# mast_panel_board.net
KiCad netlist of a schematic drawn in EAGLE
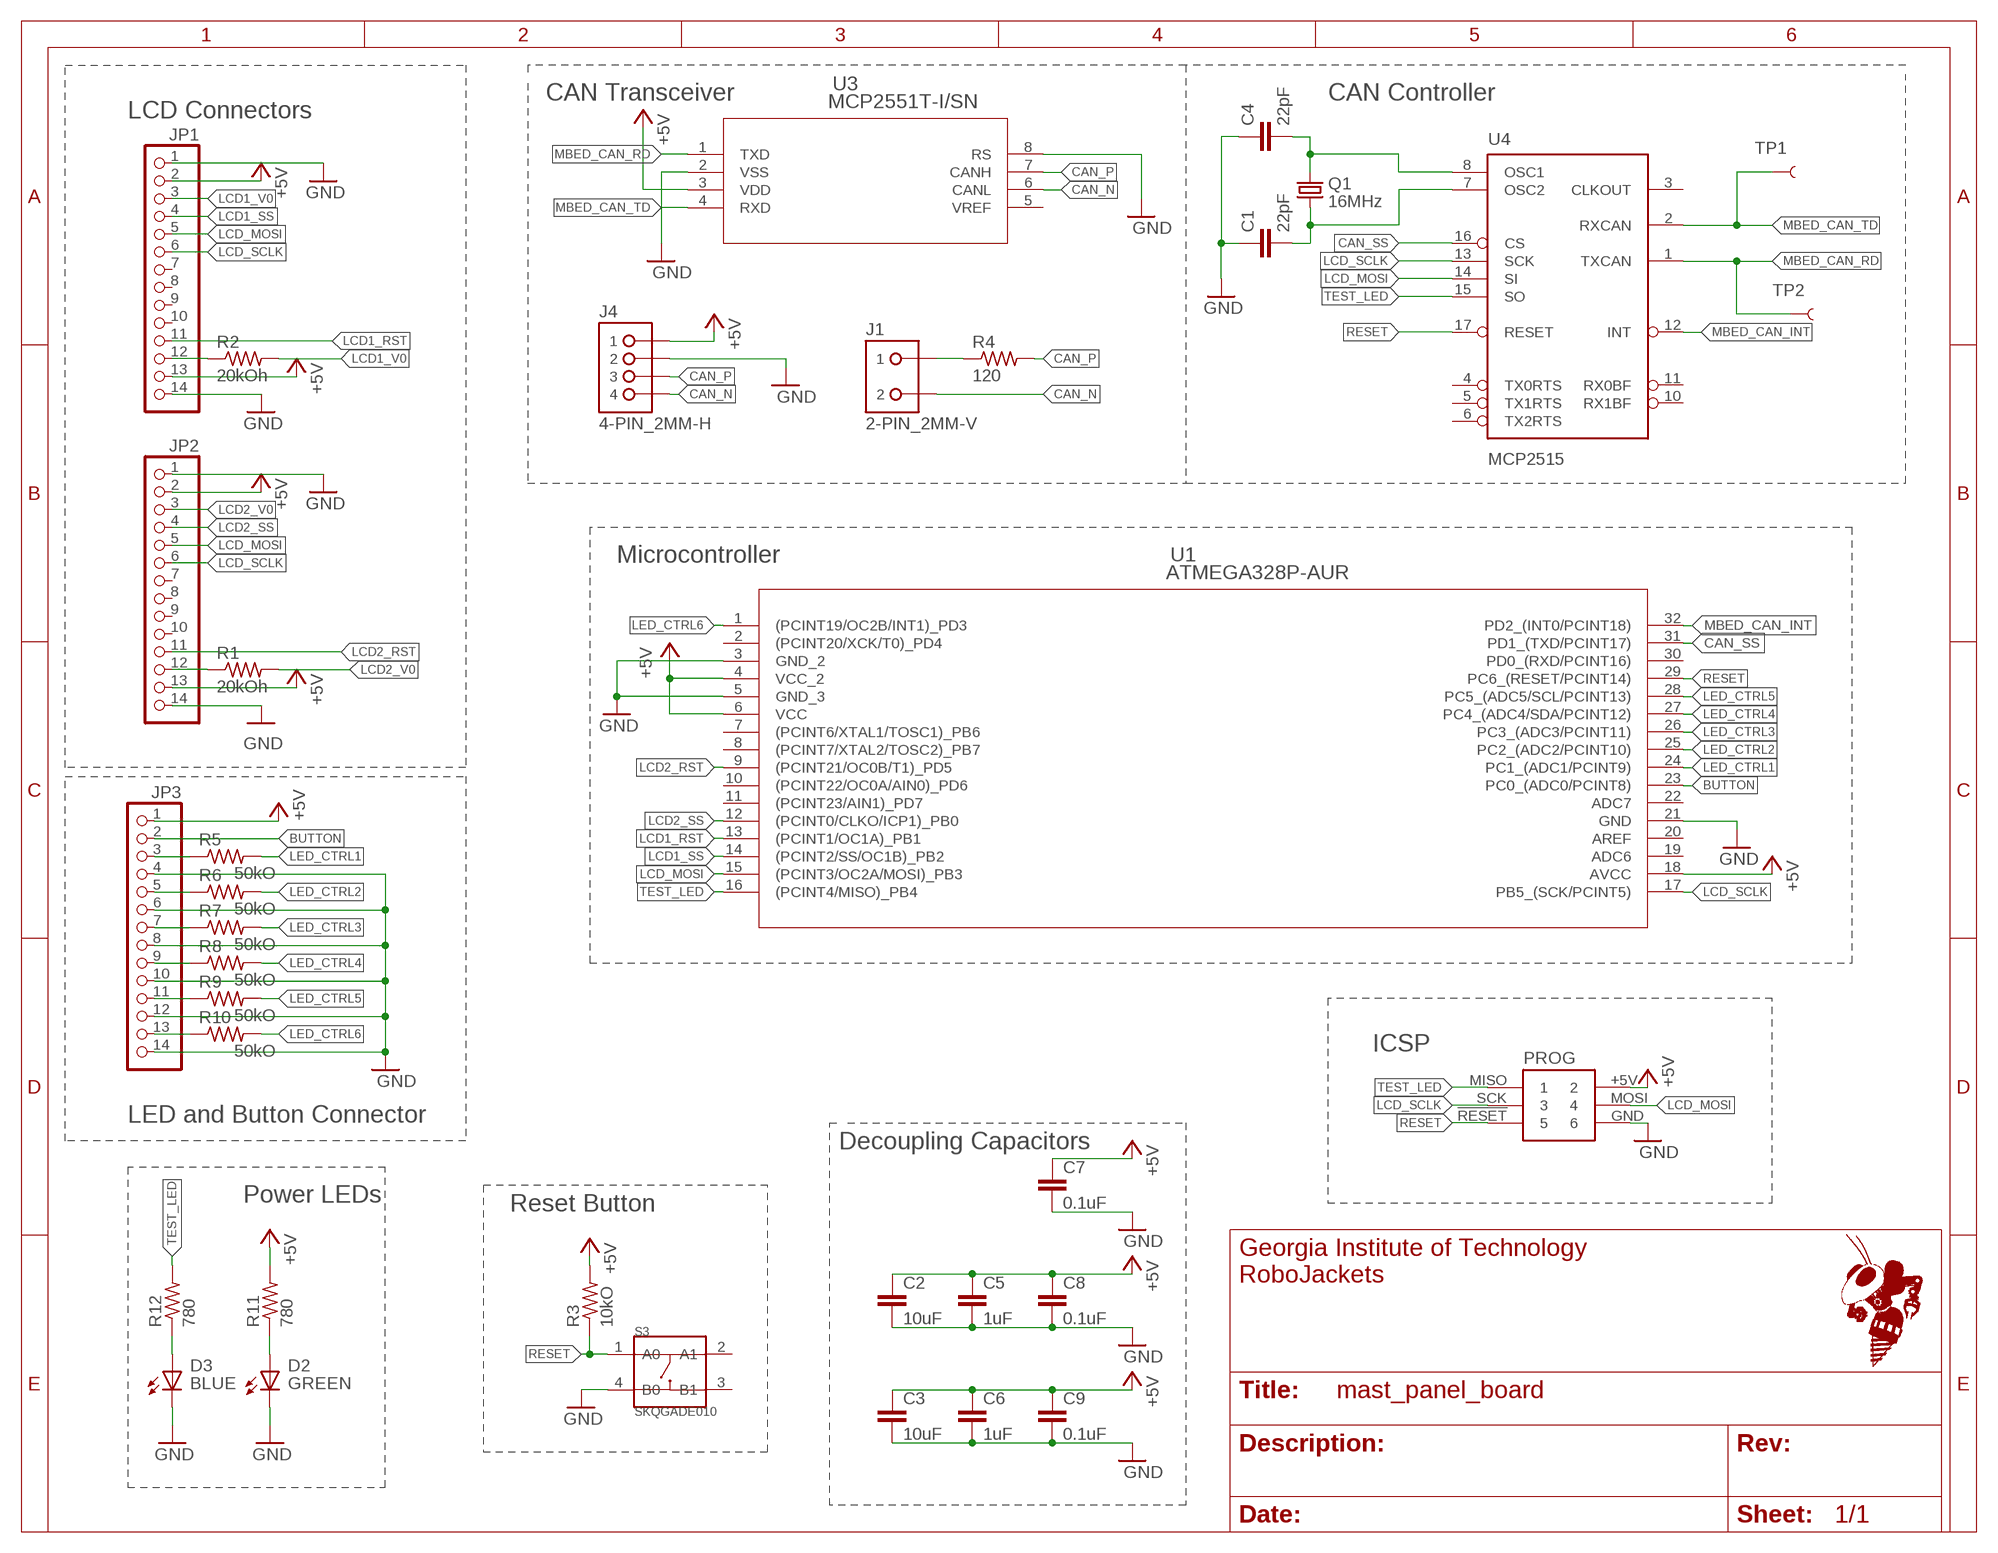
[diagram p0: schematic, sheet 1]

(export (version "E")
  (design (tool "Eeschema 10.0.6"))
  (components
    (comp (ref "C1")
      (value "22pF")
      (footprint "eagle-import:0603-CAP")
      (libsource (lib "eagle-import") (part "22PF-50V-5%(0603)"))
    )
    (comp (ref "C2")
      (value "10uF")
      (footprint "eagle-import:C0805")
      (libsource (lib "eagle-import") (part "C-EUC0805"))
    )
    (comp (ref "C3")
      (value "10uF")
      (footprint "eagle-import:C0805")
      (libsource (lib "eagle-import") (part "C-EUC0805"))
    )
    (comp (ref "C4")
      (value "22pF")
      (footprint "eagle-import:0603-CAP")
      (libsource (lib "eagle-import") (part "22PF-50V-5%(0603)"))
    )
    (comp (ref "C5")
      (value "1uF")
      (footprint "eagle-import:C0603")
      (libsource (lib "eagle-import") (part "C-EUC0603"))
    )
    (comp (ref "C6")
      (value "1uF")
      (footprint "eagle-import:C0603")
      (libsource (lib "eagle-import") (part "C-EUC0603"))
    )
    (comp (ref "C7")
      (value "0.1uF")
      (footprint "eagle-import:C0402")
      (libsource (lib "eagle-import") (part "C-EUC0402"))
    )
    (comp (ref "C8")
      (value "0.1uF")
      (footprint "eagle-import:C0402")
      (libsource (lib "eagle-import") (part "C-EUC0402"))
    )
    (comp (ref "C9")
      (value "0.1uF")
      (footprint "eagle-import:C0402")
      (libsource (lib "eagle-import") (part "C-EUC0402"))
    )
    (comp (ref "D2")
      (value "GREEN")
      (footprint "eagle-import:CHIP-LED0603")
      (fields (field (name "MPN") "LTST-C191KGKT"))
      (libsource (lib "eagle-import") (part "LED-SMD-GREEN"))
    )
    (comp (ref "D3")
      (value "BLUE")
      (footprint "eagle-import:CHIP-LED0603")
      (fields (field (name "MPN") "LTST-C191TBKT"))
      (libsource (lib "eagle-import") (part "LED-SMD-BLUE"))
    )
    (comp (ref "J1")
      (value "2-PIN_2MM-V")
      (footprint "eagle-import:2MM-2-V")
      (libsource (lib "eagle-import") (part "2-PIN_2MM-V"))
    )
    (comp (ref "J4")
      (value "4-PIN_2MM-H")
      (footprint "eagle-import:2MM-4-H")
      (fields (field (name "MPN") "0353630460"))
      (libsource (lib "eagle-import") (part "4-PIN_2MM-H"))
    )
    (comp (ref "JP1")
      (value "PINHD-1X14")
      (footprint "eagle-import:1X14")
      (libsource (lib "eagle-import") (part "PINHD-1X14"))
    )
    (comp (ref "JP2")
      (value "PINHD-1X14")
      (footprint "eagle-import:1X14")
      (libsource (lib "eagle-import") (part "PINHD-1X14"))
    )
    (comp (ref "JP3")
      (value "PINHD-1X14")
      (footprint "eagle-import:1X14")
      (libsource (lib "eagle-import") (part "PINHD-1X14"))
    )
    (comp (ref "PROG")
      (value "ICSP Connector")
      (footprint "eagle-import:2X3SHROUDED")
      (libsource (lib "eagle-import") (part "2X3SHROUDED"))
    )
    (comp (ref "Q1")
      (value "16MHz")
      (footprint "eagle-import:CRYSTAL-SMD-5X3")
      (libsource (lib "eagle-import") (part "CRYSTAL5X3"))
    )
    (comp (ref "R1")
      (value "20kOh")
      (footprint "eagle-import:R0603")
      (libsource (lib "eagle-import") (part "R-US_R0603"))
    )
    (comp (ref "R2")
      (value "20kOh")
      (footprint "eagle-import:R0603")
      (libsource (lib "eagle-import") (part "R-US_R0603"))
    )
    (comp (ref "R3")
      (value "10kO")
      (footprint "eagle-import:R0603")
      (libsource (lib "eagle-import") (part "R-US_R0603"))
    )
    (comp (ref "R4")
      (value "120")
      (footprint "eagle-import:R0603")
      (libsource (lib "eagle-import") (part "R-US_R0603"))
    )
    (comp (ref "R5")
      (value "50kO")
      (footprint "eagle-import:R0805")
      (libsource (lib "eagle-import") (part "R-US_R0805"))
    )
    (comp (ref "R6")
      (value "50kO")
      (footprint "eagle-import:R0805")
      (libsource (lib "eagle-import") (part "R-US_R0805"))
    )
    (comp (ref "R7")
      (value "50kO")
      (footprint "eagle-import:R0805")
      (libsource (lib "eagle-import") (part "R-US_R0805"))
    )
    (comp (ref "R8")
      (value "50kO")
      (footprint "eagle-import:R0805")
      (libsource (lib "eagle-import") (part "R-US_R0805"))
    )
    (comp (ref "R9")
      (value "50kO")
      (footprint "eagle-import:R0805")
      (libsource (lib "eagle-import") (part "R-US_R0805"))
    )
    (comp (ref "R10")
      (value "50kO")
      (footprint "eagle-import:R0805")
      (libsource (lib "eagle-import") (part "R-US_R0805"))
    )
    (comp (ref "R11")
      (value "780")
      (footprint "eagle-import:R0402")
      (libsource (lib "eagle-import") (part "R-US_R0402"))
    )
    (comp (ref "R12")
      (value "780")
      (footprint "eagle-import:R0402")
      (libsource (lib "eagle-import") (part "R-US_R0402"))
    )
    (comp (ref "S3")
      (value "SKQGADE010")
      (footprint "eagle-import:SW4-SMD-5.2X5.2X1.5MM")
      (libsource (lib "eagle-import") (part "SMD-SWITCH-TOP-260GF(4P-D5.2MM)"))
    )
    (comp (ref "TP1")
      (value "TEST-POINT3X5")
      (footprint "eagle-import:PAD.03X.05")
      (libsource (lib "eagle-import") (part "TEST-POINT3X5"))
    )
    (comp (ref "TP2")
      (value "TEST-POINT3X5")
      (footprint "eagle-import:PAD.03X.05")
      (libsource (lib "eagle-import") (part "TEST-POINT3X5"))
    )
    (comp (ref "U1")
      (value "ATMEGA328P-AUR")
      (footprint "eagle-import:32A")
      (libsource (lib "eagle-import") (part "ATMEGA328P-AUR"))
    )
    (comp (ref "U3")
      (value "MCP2551T-I/SN")
      (footprint "eagle-import:SOIC8-N_MC")
      (fields (field (name "MANUFACTURER_PART_NUMBER") "MCP2551TISN"))
      (libsource (lib "eagle-import") (part "MCP2551T-I/SN"))
    )
    (comp (ref "U4")
      (value "MCP2515")
      (footprint "eagle-import:SO-18W")
      (libsource (lib "eagle-import") (part "MCP2510SO"))
    )
  )
  (nets
    (net (code "1") (name "+5V") (class "Default")
      (node (ref "C2") (pin "1") (pinfunction "1_1") (pintype "passive"))
      (node (ref "C3") (pin "1") (pinfunction "1_1") (pintype "passive"))
      (node (ref "C5") (pin "1") (pinfunction "1_1") (pintype "passive"))
      (node (ref "C6") (pin "1") (pinfunction "1_1") (pintype "passive"))
      (node (ref "C7") (pin "1") (pinfunction "1_1") (pintype "passive"))
      (node (ref "C8") (pin "1") (pinfunction "1_1") (pintype "passive"))
      (node (ref "C9") (pin "1") (pinfunction "1_1") (pintype "passive"))
      (node (ref "J4") (pin "1") (pinfunction "1_1") (pintype "passive"))
      (node (ref "JP1") (pin "13") (pinfunction "13_13") (pintype "passive"))
      (node (ref "JP1") (pin "2") (pinfunction "2_2") (pintype "passive"))
      (node (ref "JP2") (pin "13") (pinfunction "13_13") (pintype "passive"))
      (node (ref "JP2") (pin "2") (pinfunction "2_2") (pintype "passive"))
      (node (ref "JP3") (pin "1") (pinfunction "1_1") (pintype "passive"))
      (node (ref "PROG") (pin "+5V") (pinfunction "2_+5V") (pintype "bidirectional"))
      (node (ref "R11") (pin "2") (pinfunction "2_2") (pintype "passive"))
      (node (ref "R3") (pin "2") (pinfunction "2_2") (pintype "passive"))
      (node (ref "U1") (pin "18") (pinfunction "AVCC_18") (pintype "power_in"))
      (node (ref "U1") (pin "4") (pinfunction "VCC_2_4") (pintype "power_in"))
      (node (ref "U1") (pin "6") (pinfunction "VCC_6") (pintype "power_in"))
      (node (ref "U3") (pin "3") (pinfunction "VDD_3") (pintype "passive"))
    )
    (net (code "2") (name "BUTTON") (class "Default")
      (node (ref "JP3") (pin "2") (pinfunction "2_2") (pintype "passive"))
      (node (ref "U1") (pin "23") (pinfunction "PC0_(ADC0/PCINT8)_23") (pintype "bidirectional"))
    )
    (net (code "3") (name "CAN_N") (class "Default")
      (node (ref "J1") (pin "2") (pinfunction "2_2") (pintype "bidirectional"))
      (node (ref "J4") (pin "4") (pinfunction "4_4") (pintype "passive"))
      (node (ref "U3") (pin "6") (pinfunction "CANL_6") (pintype "passive"))
    )
    (net (code "4") (name "CAN_P") (class "Default")
      (node (ref "J4") (pin "3") (pinfunction "3_3") (pintype "passive"))
      (node (ref "R4") (pin "2") (pinfunction "2_2") (pintype "passive"))
      (node (ref "U3") (pin "7") (pinfunction "CANH_7") (pintype "passive"))
    )
    (net (code "5") (name "CAN_SS") (class "Default")
      (node (ref "U1") (pin "31") (pinfunction "PD1_(TXD/PCINT17)_31") (pintype "bidirectional"))
      (node (ref "U4") (pin "16") (pinfunction "CS_16") (pintype "input"))
    )
    (net (code "6") (name "GND") (class "Default")
      (node (ref "C1") (pin "1") (pinfunction "1_1") (pintype "passive"))
      (node (ref "C2") (pin "2") (pinfunction "2_2") (pintype "passive"))
      (node (ref "C3") (pin "2") (pinfunction "2_2") (pintype "passive"))
      (node (ref "C4") (pin "1") (pinfunction "1_1") (pintype "passive"))
      (node (ref "C5") (pin "2") (pinfunction "2_2") (pintype "passive"))
      (node (ref "C6") (pin "2") (pinfunction "2_2") (pintype "passive"))
      (node (ref "C7") (pin "2") (pinfunction "2_2") (pintype "passive"))
      (node (ref "C8") (pin "2") (pinfunction "2_2") (pintype "passive"))
      (node (ref "C9") (pin "2") (pinfunction "2_2") (pintype "passive"))
      (node (ref "D2") (pin "C") (pinfunction "K_C") (pintype "passive"))
      (node (ref "D3") (pin "C") (pinfunction "K_C") (pintype "passive"))
      (node (ref "J4") (pin "2") (pinfunction "2_2") (pintype "passive"))
      (node (ref "JP1") (pin "1") (pinfunction "1_1") (pintype "passive"))
      (node (ref "JP1") (pin "14") (pinfunction "14_14") (pintype "passive"))
      (node (ref "JP2") (pin "1") (pinfunction "1_1") (pintype "passive"))
      (node (ref "JP2") (pin "14") (pinfunction "14_14") (pintype "passive"))
      (node (ref "JP3") (pin "10") (pinfunction "10_10") (pintype "passive"))
      (node (ref "JP3") (pin "12") (pinfunction "12_12") (pintype "passive"))
      (node (ref "JP3") (pin "14") (pinfunction "14_14") (pintype "passive"))
      (node (ref "JP3") (pin "4") (pinfunction "4_4") (pintype "passive"))
      (node (ref "JP3") (pin "6") (pinfunction "6_6") (pintype "passive"))
      (node (ref "JP3") (pin "8") (pinfunction "8_8") (pintype "passive"))
      (node (ref "PROG") (pin "GND") (pinfunction "6_GND") (pintype "bidirectional"))
      (node (ref "S3") (pin "4") (pinfunction "B0_4") (pintype "bidirectional"))
      (node (ref "U1") (pin "21") (pinfunction "GND_21") (pintype "power_in"))
      (node (ref "U1") (pin "3") (pinfunction "GND_2_3") (pintype "power_in"))
      (node (ref "U1") (pin "5") (pinfunction "GND_3_5") (pintype "power_in"))
      (node (ref "U3") (pin "2") (pinfunction "VSS_2") (pintype "passive"))
      (node (ref "U3") (pin "8") (pinfunction "RS_8") (pintype "passive"))
    )
    (net (code "7") (name "LCD1_RST") (class "Default")
      (node (ref "JP1") (pin "11") (pinfunction "11_11") (pintype "passive"))
      (node (ref "U1") (pin "13") (pinfunction "(PCINT1/OC1A)_PB1_13") (pintype "bidirectional"))
    )
    (net (code "8") (name "LCD1_SS") (class "Default")
      (node (ref "JP1") (pin "4") (pinfunction "4_4") (pintype "passive"))
      (node (ref "U1") (pin "14") (pinfunction "(PCINT2/SS/OC1B)_PB2_14") (pintype "bidirectional"))
    )
    (net (code "9") (name "LCD1_V0") (class "Default")
      (node (ref "JP1") (pin "3") (pinfunction "3_3") (pintype "passive"))
      (node (ref "R2") (pin "2") (pinfunction "2_2") (pintype "passive"))
    )
    (net (code "10") (name "LCD2_RST") (class "Default")
      (node (ref "JP2") (pin "11") (pinfunction "11_11") (pintype "passive"))
      (node (ref "U1") (pin "9") (pinfunction "(PCINT21/OC0B/T1)_PD5_9") (pintype "bidirectional"))
    )
    (net (code "11") (name "LCD2_SS") (class "Default")
      (node (ref "JP2") (pin "4") (pinfunction "4_4") (pintype "passive"))
      (node (ref "U1") (pin "12") (pinfunction "(PCINT0/CLKO/ICP1)_PB0_12") (pintype "bidirectional"))
    )
    (net (code "12") (name "LCD2_V0") (class "Default")
      (node (ref "JP2") (pin "3") (pinfunction "3_3") (pintype "passive"))
      (node (ref "R1") (pin "2") (pinfunction "2_2") (pintype "passive"))
    )
    (net (code "13") (name "LCD_MOSI") (class "Default")
      (node (ref "JP1") (pin "5") (pinfunction "5_5") (pintype "passive"))
      (node (ref "JP2") (pin "5") (pinfunction "5_5") (pintype "passive"))
      (node (ref "PROG") (pin "MOSI") (pinfunction "4_MOSI") (pintype "bidirectional"))
      (node (ref "U1") (pin "15") (pinfunction "(PCINT3/OC2A/MOSI)_PB3_15") (pintype "bidirectional"))
      (node (ref "U4") (pin "14") (pinfunction "SI_14") (pintype "input"))
    )
    (net (code "14") (name "LCD_SCLK") (class "Default")
      (node (ref "JP1") (pin "6") (pinfunction "6_6") (pintype "passive"))
      (node (ref "JP2") (pin "6") (pinfunction "6_6") (pintype "passive"))
      (node (ref "PROG") (pin "SCK") (pinfunction "3_SCK") (pintype "bidirectional"))
      (node (ref "U1") (pin "17") (pinfunction "PB5_(SCK/PCINT5)_17") (pintype "bidirectional"))
      (node (ref "U4") (pin "13") (pinfunction "SCK_13") (pintype "input"))
    )
    (net (code "15") (name "LED_CTRL1") (class "Default")
      (node (ref "R5") (pin "2") (pinfunction "2_2") (pintype "passive"))
      (node (ref "U1") (pin "24") (pinfunction "PC1_(ADC1/PCINT9)_24") (pintype "bidirectional"))
    )
    (net (code "16") (name "LED_CTRL2") (class "Default")
      (node (ref "R6") (pin "2") (pinfunction "2_2") (pintype "passive"))
      (node (ref "U1") (pin "25") (pinfunction "PC2_(ADC2/PCINT10)_25") (pintype "bidirectional"))
    )
    (net (code "17") (name "LED_CTRL3") (class "Default")
      (node (ref "R7") (pin "2") (pinfunction "2_2") (pintype "passive"))
      (node (ref "U1") (pin "26") (pinfunction "PC3_(ADC3/PCINT11)_26") (pintype "bidirectional"))
    )
    (net (code "18") (name "LED_CTRL4") (class "Default")
      (node (ref "R8") (pin "2") (pinfunction "2_2") (pintype "passive"))
      (node (ref "U1") (pin "27") (pinfunction "PC4_(ADC4/SDA/PCINT12)_27") (pintype "bidirectional"))
    )
    (net (code "19") (name "LED_CTRL5") (class "Default")
      (node (ref "R9") (pin "2") (pinfunction "2_2") (pintype "passive"))
      (node (ref "U1") (pin "28") (pinfunction "PC5_(ADC5/SCL/PCINT13)_28") (pintype "bidirectional"))
    )
    (net (code "20") (name "LED_CTRL6") (class "Default")
      (node (ref "R10") (pin "2") (pinfunction "2_2") (pintype "passive"))
      (node (ref "U1") (pin "1") (pinfunction "(PCINT19/OC2B/INT1)_PD3_1") (pintype "bidirectional"))
    )
    (net (code "21") (name "MBED_CAN_INT") (class "Default")
      (node (ref "U1") (pin "32") (pinfunction "PD2_(INT0/PCINT18)_32") (pintype "bidirectional"))
      (node (ref "U4") (pin "12") (pinfunction "INT_12") (pintype "output"))
    )
    (net (code "22") (name "MBED_CAN_RD") (class "Default")
      (node (ref "TP2") (pin "P$1") (pinfunction "1_P$1") (pintype "bidirectional"))
      (node (ref "U3") (pin "1") (pinfunction "TXD_1") (pintype "passive"))
      (node (ref "U4") (pin "1") (pinfunction "TXCAN_1") (pintype "output"))
    )
    (net (code "23") (name "MBED_CAN_TD") (class "Default")
      (node (ref "TP1") (pin "P$1") (pinfunction "1_P$1") (pintype "bidirectional"))
      (node (ref "U3") (pin "4") (pinfunction "RXD_4") (pintype "passive"))
      (node (ref "U4") (pin "2") (pinfunction "RXCAN_2") (pintype "input"))
    )
    (net (code "24") (name "Net-(D2-PadA)") (class "Default")
      (node (ref "D2") (pin "A") (pinfunction "A_A") (pintype "passive"))
      (node (ref "R11") (pin "1") (pinfunction "1_1") (pintype "passive"))
    )
    (net (code "25") (name "Net-(D3-PadA)") (class "Default")
      (node (ref "D3") (pin "A") (pinfunction "A_A") (pintype "passive"))
      (node (ref "R12") (pin "1") (pinfunction "1_1") (pintype "passive"))
    )
    (net (code "26") (name "Net-(J1-Pad1)") (class "Default")
      (node (ref "J1") (pin "1") (pinfunction "1_1") (pintype "bidirectional"))
      (node (ref "R4") (pin "1") (pinfunction "1_1") (pintype "passive"))
    )
    (net (code "27") (name "Net-(JP1-Pad12)") (class "Default")
      (node (ref "JP1") (pin "12") (pinfunction "12_12") (pintype "passive"))
      (node (ref "R2") (pin "1") (pinfunction "1_1") (pintype "passive"))
    )
    (net (code "28") (name "Net-(JP2-Pad12)") (class "Default")
      (node (ref "JP2") (pin "12") (pinfunction "12_12") (pintype "passive"))
      (node (ref "R1") (pin "1") (pinfunction "1_1") (pintype "passive"))
    )
    (net (code "29") (name "Net-(JP3-Pad3)") (class "Default")
      (node (ref "JP3") (pin "3") (pinfunction "3_3") (pintype "passive"))
      (node (ref "R5") (pin "1") (pinfunction "1_1") (pintype "passive"))
    )
    (net (code "30") (name "Net-(JP3-Pad5)") (class "Default")
      (node (ref "JP3") (pin "5") (pinfunction "5_5") (pintype "passive"))
      (node (ref "R6") (pin "1") (pinfunction "1_1") (pintype "passive"))
    )
    (net (code "31") (name "Net-(JP3-Pad7)") (class "Default")
      (node (ref "JP3") (pin "7") (pinfunction "7_7") (pintype "passive"))
      (node (ref "R7") (pin "1") (pinfunction "1_1") (pintype "passive"))
    )
    (net (code "32") (name "Net-(JP3-Pad9)") (class "Default")
      (node (ref "JP3") (pin "9") (pinfunction "9_9") (pintype "passive"))
      (node (ref "R8") (pin "1") (pinfunction "1_1") (pintype "passive"))
    )
    (net (code "33") (name "Net-(JP3-Pad11)") (class "Default")
      (node (ref "JP3") (pin "11") (pinfunction "11_11") (pintype "passive"))
      (node (ref "R9") (pin "1") (pinfunction "1_1") (pintype "passive"))
    )
    (net (code "34") (name "Net-(JP3-Pad13)") (class "Default")
      (node (ref "JP3") (pin "13") (pinfunction "13_13") (pintype "passive"))
      (node (ref "R10") (pin "1") (pinfunction "1_1") (pintype "passive"))
    )
    (net (code "35") (name "Net-(Q1-2)") (class "Default")
      (node (ref "C4") (pin "2") (pinfunction "2_2") (pintype "passive"))
      (node (ref "Q1") (pin "3") (pinfunction "2_3") (pintype "passive"))
      (node (ref "U4") (pin "8") (pinfunction "OSC1_8") (pintype "input"))
    )
    (net (code "36") (name "Net-(U4A-OSC2)") (class "Default")
      (node (ref "C1") (pin "2") (pinfunction "2_2") (pintype "passive"))
      (node (ref "Q1") (pin "1") (pinfunction "1_1") (pintype "passive"))
      (node (ref "U4") (pin "7") (pinfunction "OSC2_7") (pintype "output"))
    )
    (net (code "37") (name "RESET") (class "Default")
      (node (ref "PROG") (pin "!RESET") (pinfunction "5_!RESET") (pintype "bidirectional"))
      (node (ref "R3") (pin "1") (pinfunction "1_1") (pintype "passive"))
      (node (ref "S3") (pin "1") (pinfunction "A0_1") (pintype "bidirectional"))
      (node (ref "U1") (pin "29") (pinfunction "PC6_(RESET/PCINT14)_29") (pintype "bidirectional"))
      (node (ref "U4") (pin "17") (pinfunction "RESET_17") (pintype "input"))
    )
    (net (code "38") (name "TEST_LED") (class "Default")
      (node (ref "PROG") (pin "MISO") (pinfunction "1_MISO") (pintype "bidirectional"))
      (node (ref "R12") (pin "2") (pinfunction "2_2") (pintype "passive"))
      (node (ref "U1") (pin "16") (pinfunction "(PCINT4/MISO)_PB4_16") (pintype "bidirectional"))
      (node (ref "U4") (pin "15") (pinfunction "SO_15") (pintype "output"))
    )
    (net (code "39") (name "unconnected-(JP1-Pad7)") (class "Default")
      (node (ref "JP1") (pin "7") (pinfunction "7_7") (pintype "passive"))
    )
    (net (code "40") (name "unconnected-(JP1-Pad8)") (class "Default")
      (node (ref "JP1") (pin "8") (pinfunction "8_8") (pintype "passive"))
    )
    (net (code "41") (name "unconnected-(JP1-Pad9)") (class "Default")
      (node (ref "JP1") (pin "9") (pinfunction "9_9") (pintype "passive"))
    )
    (net (code "42") (name "unconnected-(JP1-Pad10)") (class "Default")
      (node (ref "JP1") (pin "10") (pinfunction "10_10") (pintype "passive"))
    )
    (net (code "43") (name "unconnected-(JP2-Pad7)") (class "Default")
      (node (ref "JP2") (pin "7") (pinfunction "7_7") (pintype "passive"))
    )
    (net (code "44") (name "unconnected-(JP2-Pad8)") (class "Default")
      (node (ref "JP2") (pin "8") (pinfunction "8_8") (pintype "passive"))
    )
    (net (code "45") (name "unconnected-(JP2-Pad9)") (class "Default")
      (node (ref "JP2") (pin "9") (pinfunction "9_9") (pintype "passive"))
    )
    (net (code "46") (name "unconnected-(JP2-Pad10)") (class "Default")
      (node (ref "JP2") (pin "10") (pinfunction "10_10") (pintype "passive"))
    )
    (net (code "47") (name "unconnected-(S3-A1-Pad2)") (class "Default")
      (node (ref "S3") (pin "2") (pinfunction "A1_2") (pintype "bidirectional"))
    )
    (net (code "48") (name "unconnected-(S3-B1-Pad3)") (class "Default")
      (node (ref "S3") (pin "3") (pinfunction "B1_3") (pintype "bidirectional"))
    )
    (net (code "49") (name "unconnected-(U1-(PCINT6{slash}XTAL1{slash}TOSC1)_PB6-Pad7)") (class "Default")
      (node (ref "U1") (pin "7") (pinfunction "(PCINT6/XTAL1/TOSC1)_PB6_7") (pintype "bidirectional"))
    )
    (net (code "50") (name "unconnected-(U1-(PCINT7{slash}XTAL2{slash}TOSC2)_PB7-Pad8)") (class "Default")
      (node (ref "U1") (pin "8") (pinfunction "(PCINT7/XTAL2/TOSC2)_PB7_8") (pintype "bidirectional"))
    )
    (net (code "51") (name "unconnected-(U1-(PCINT20{slash}XCK{slash}T0)_PD4-Pad2)") (class "Default")
      (node (ref "U1") (pin "2") (pinfunction "(PCINT20/XCK/T0)_PD4_2") (pintype "bidirectional"))
    )
    (net (code "52") (name "unconnected-(U1-(PCINT22{slash}OC0A{slash}AIN0)_PD6-Pad10)") (class "Default")
      (node (ref "U1") (pin "10") (pinfunction "(PCINT22/OC0A/AIN0)_PD6_10") (pintype "bidirectional"))
    )
    (net (code "53") (name "unconnected-(U1-(PCINT23{slash}AIN1)_PD7-Pad11)") (class "Default")
      (node (ref "U1") (pin "11") (pinfunction "(PCINT23/AIN1)_PD7_11") (pintype "bidirectional"))
    )
    (net (code "54") (name "unconnected-(U1-ADC6-Pad19)") (class "Default")
      (node (ref "U1") (pin "19") (pinfunction "ADC6_19") (pintype "input"))
    )
    (net (code "55") (name "unconnected-(U1-ADC7-Pad22)") (class "Default")
      (node (ref "U1") (pin "22") (pinfunction "ADC7_22") (pintype "input"))
    )
    (net (code "56") (name "unconnected-(U1-AREF-Pad20)") (class "Default")
      (node (ref "U1") (pin "20") (pinfunction "AREF_20") (pintype "passive"))
    )
    (net (code "57") (name "unconnected-(U1-PD0_(RXD{slash}PCINT16)-Pad30)") (class "Default")
      (node (ref "U1") (pin "30") (pinfunction "PD0_(RXD/PCINT16)_30") (pintype "bidirectional"))
    )
    (net (code "58") (name "unconnected-(U3-VREF-Pad5)") (class "Default")
      (node (ref "U3") (pin "5") (pinfunction "VREF_5") (pintype "passive"))
    )
    (net (code "59") (name "unconnected-(U4A-CLKOUT-Pad3)") (class "Default")
      (node (ref "U4") (pin "3") (pinfunction "CLKOUT_3") (pintype "output"))
    )
    (net (code "60") (name "unconnected-(U4A-RX0BF-Pad11)") (class "Default")
      (node (ref "U4") (pin "11") (pinfunction "RX0BF_11") (pintype "output"))
    )
    (net (code "61") (name "unconnected-(U4A-RX1BF-Pad10)") (class "Default")
      (node (ref "U4") (pin "10") (pinfunction "RX1BF_10") (pintype "output"))
    )
    (net (code "62") (name "unconnected-(U4A-TX0RTS-Pad4)") (class "Default")
      (node (ref "U4") (pin "4") (pinfunction "TX0RTS_4") (pintype "input"))
    )
    (net (code "63") (name "unconnected-(U4A-TX1RTS-Pad5)") (class "Default")
      (node (ref "U4") (pin "5") (pinfunction "TX1RTS_5") (pintype "input"))
    )
    (net (code "64") (name "unconnected-(U4A-TX2RTS-Pad6)") (class "Default")
      (node (ref "U4") (pin "6") (pinfunction "TX2RTS_6") (pintype "input"))
    )
  )
)
